# tc0xC_prod.net
KiCad netlist of a schematic drawn in EAGLE
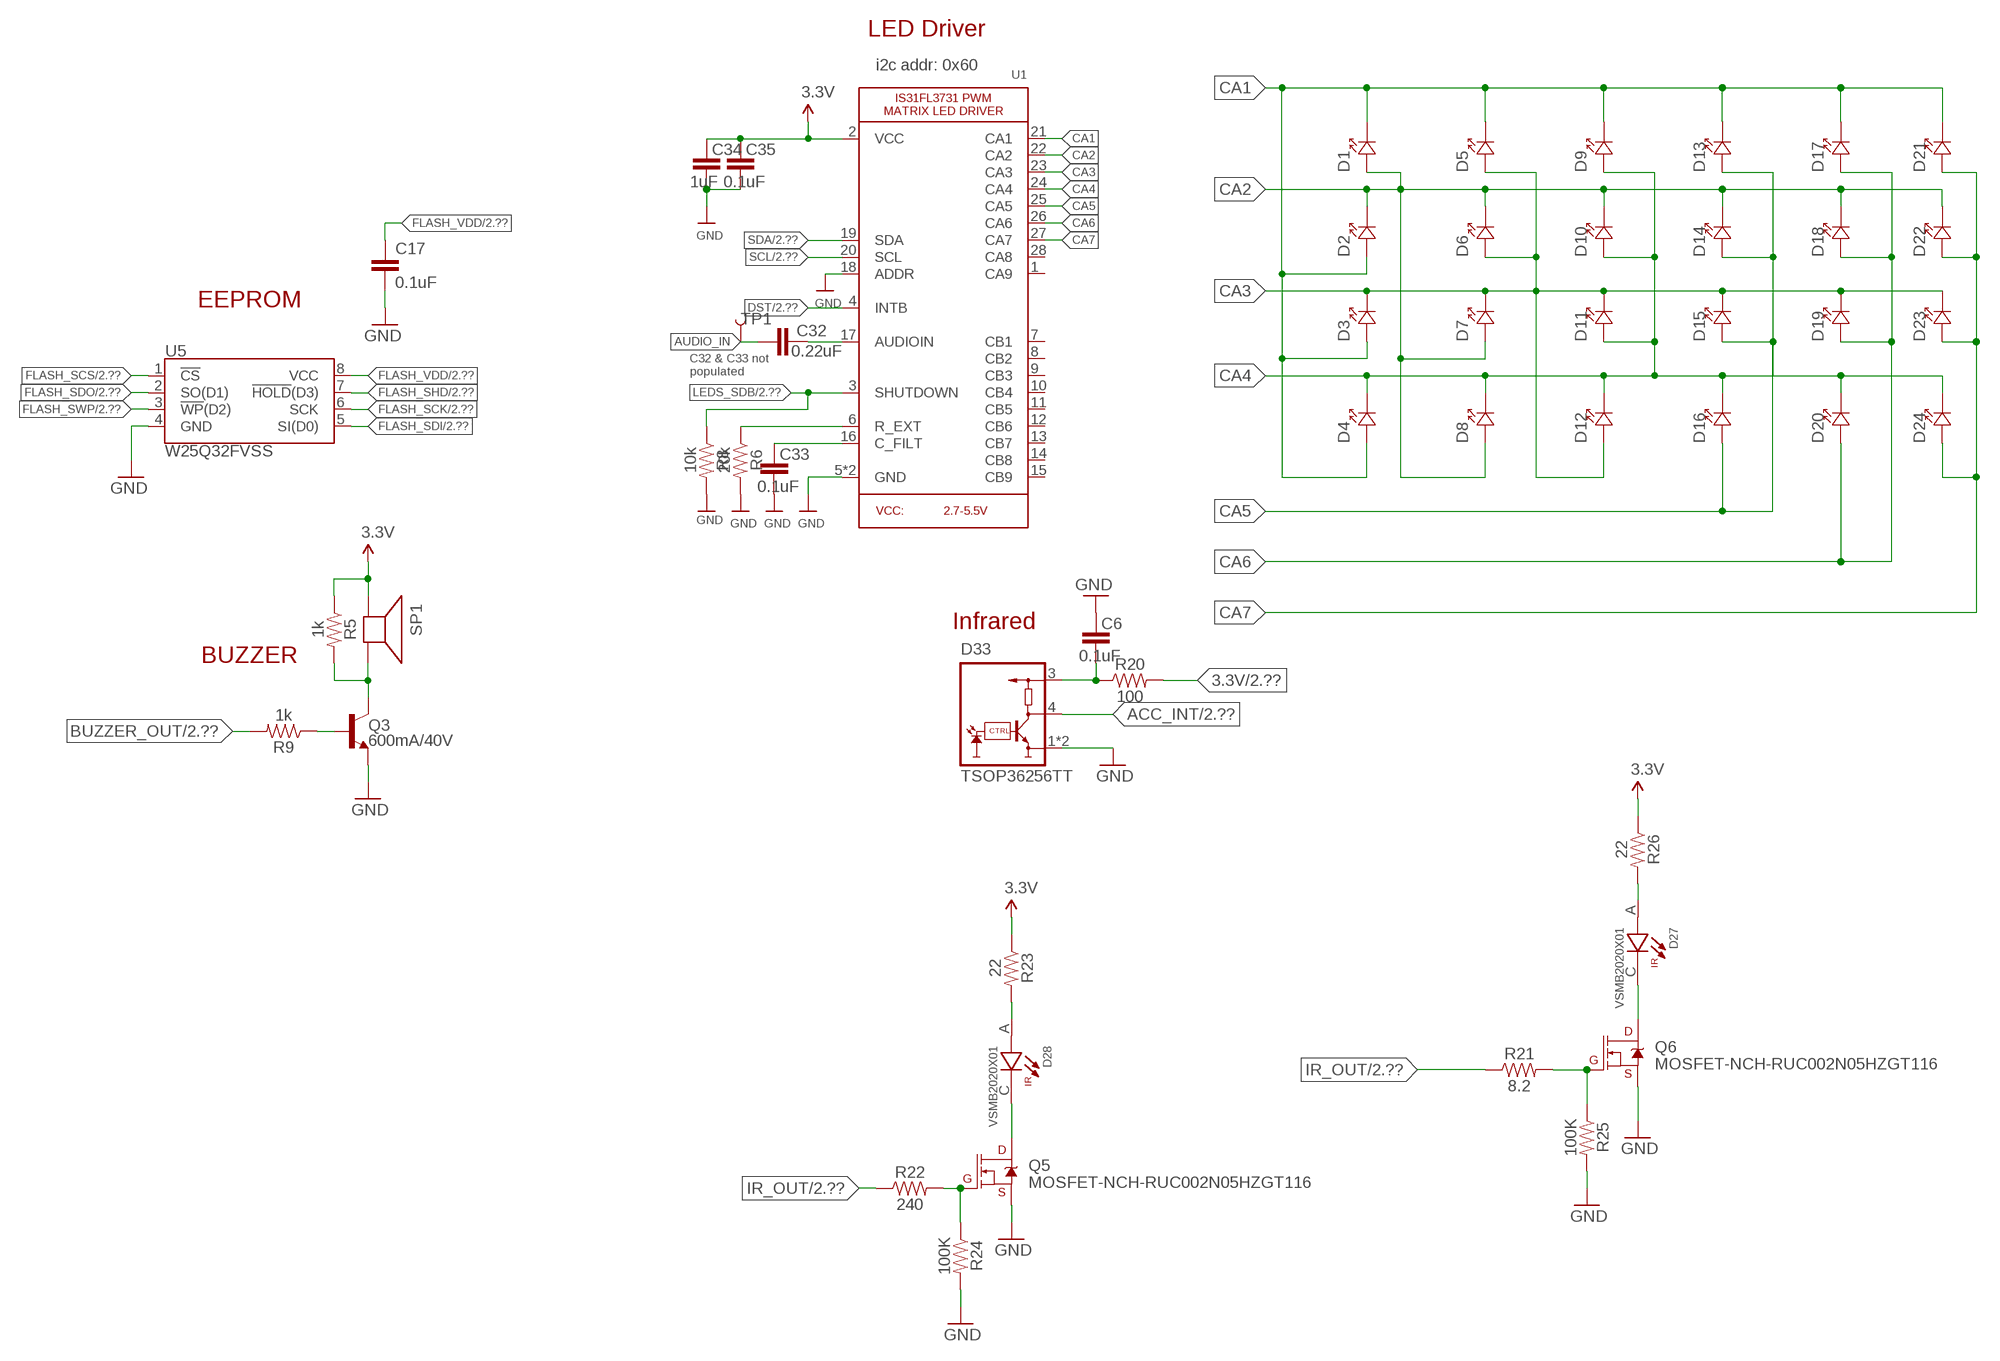
[diagram p0: schematic, sheet 1]
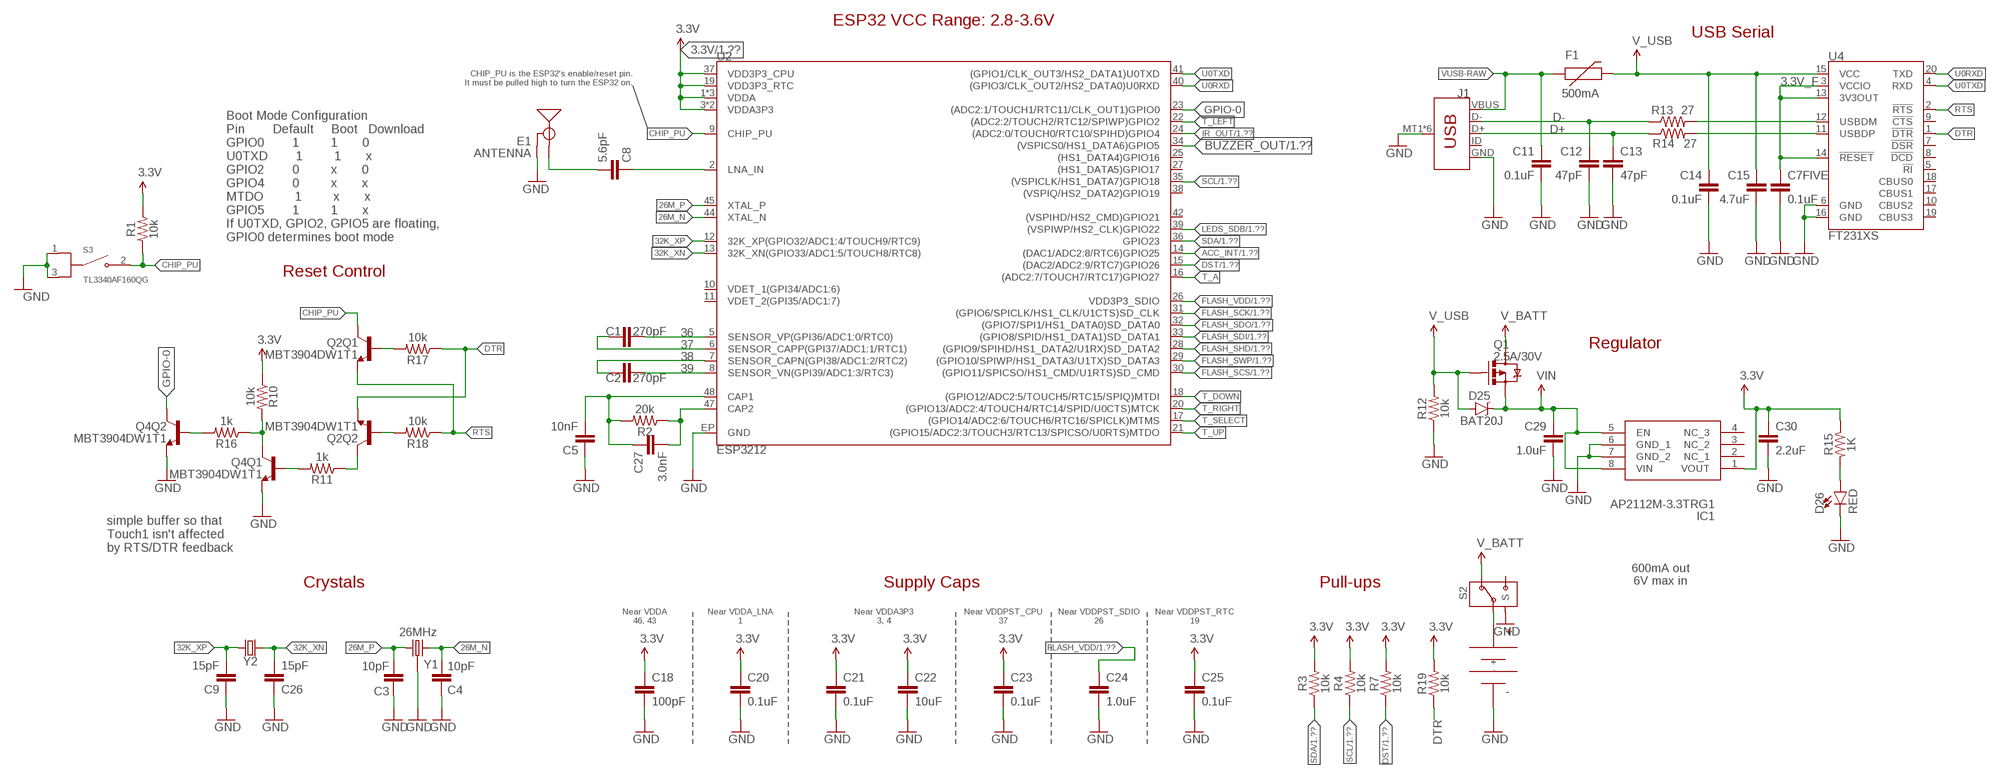
[diagram p1: schematic, sheet 2]

(export (version "E")
  (design (tool "Eeschema 10.0.6"))
  (components
    (comp (ref "C6")
      (value "0.1uF")
      (footprint "eagle-import:0603")
      (libsource (lib "eagle-import") (part "10PF-0603-50V-5%"))
    )
    (comp (ref "C17")
      (value "0.1uF")
      (footprint "eagle-import:0603")
      (libsource (lib "eagle-import") (part "0.1UF-0603-25V-(+80/-20%)"))
    )
    (comp (ref "C32")
      (value "0.22uF")
      (footprint "eagle-import:0603")
      (libsource (lib "eagle-import") (part "10PF-0603-50V-5%"))
    )
    (comp (ref "C33")
      (value "0.1uF")
      (footprint "eagle-import:0603")
      (libsource (lib "eagle-import") (part "10PF-0603-50V-5%"))
    )
    (comp (ref "C34")
      (value "1uF")
      (footprint "eagle-import:0603")
      (libsource (lib "eagle-import") (part "10PF-0603-50V-5%"))
    )
    (comp (ref "C35")
      (value "0.1uF")
      (footprint "eagle-import:0603")
      (libsource (lib "eagle-import") (part "10PF-0603-50V-5%"))
    )
    (comp (ref "D1")
      (value "LED-603")
      (footprint "eagle-import:SMD-603")
      (libsource (lib "eagle-import") (part "LED-603"))
    )
    (comp (ref "D2")
      (value "LED-603")
      (footprint "eagle-import:SMD-603")
      (libsource (lib "eagle-import") (part "LED-603"))
    )
    (comp (ref "D3")
      (value "LED-603")
      (footprint "eagle-import:SMD-603")
      (libsource (lib "eagle-import") (part "LED-603"))
    )
    (comp (ref "D4")
      (value "LED-603")
      (footprint "eagle-import:SMD-603")
      (libsource (lib "eagle-import") (part "LED-603"))
    )
    (comp (ref "D5")
      (value "LED-603")
      (footprint "eagle-import:SMD-603")
      (libsource (lib "eagle-import") (part "LED-603"))
    )
    (comp (ref "D6")
      (value "LED-603")
      (footprint "eagle-import:SMD-603")
      (libsource (lib "eagle-import") (part "LED-603"))
    )
    (comp (ref "D7")
      (value "LED-603")
      (footprint "eagle-import:SMD-603")
      (libsource (lib "eagle-import") (part "LED-603"))
    )
    (comp (ref "D8")
      (value "LED-603")
      (footprint "eagle-import:SMD-603")
      (libsource (lib "eagle-import") (part "LED-603"))
    )
    (comp (ref "D9")
      (value "LED-603")
      (footprint "eagle-import:SMD-603")
      (libsource (lib "eagle-import") (part "LED-603"))
    )
    (comp (ref "D10")
      (value "LED-603")
      (footprint "eagle-import:SMD-603")
      (libsource (lib "eagle-import") (part "LED-603"))
    )
    (comp (ref "D11")
      (value "LED-603")
      (footprint "eagle-import:SMD-603")
      (libsource (lib "eagle-import") (part "LED-603"))
    )
    (comp (ref "D12")
      (value "LED-603")
      (footprint "eagle-import:SMD-603")
      (libsource (lib "eagle-import") (part "LED-603"))
    )
    (comp (ref "D13")
      (value "LED-603")
      (footprint "eagle-import:SMD-603")
      (libsource (lib "eagle-import") (part "LED-603"))
    )
    (comp (ref "D14")
      (value "LED-603")
      (footprint "eagle-import:SMD-603")
      (libsource (lib "eagle-import") (part "LED-603"))
    )
    (comp (ref "D15")
      (value "LED-603")
      (footprint "eagle-import:SMD-603")
      (libsource (lib "eagle-import") (part "LED-603"))
    )
    (comp (ref "D16")
      (value "LED-603")
      (footprint "eagle-import:SMD-603")
      (libsource (lib "eagle-import") (part "LED-603"))
    )
    (comp (ref "D17")
      (value "LED-603")
      (footprint "eagle-import:SMD-603")
      (libsource (lib "eagle-import") (part "LED-603"))
    )
    (comp (ref "D18")
      (value "LED-603")
      (footprint "eagle-import:SMD-603")
      (libsource (lib "eagle-import") (part "LED-603"))
    )
    (comp (ref "D19")
      (value "LED-603")
      (footprint "eagle-import:SMD-603")
      (libsource (lib "eagle-import") (part "LED-603"))
    )
    (comp (ref "D20")
      (value "LED-603")
      (footprint "eagle-import:SMD-603")
      (libsource (lib "eagle-import") (part "LED-603"))
    )
    (comp (ref "D21")
      (value "LED-603")
      (footprint "eagle-import:SMD-603")
      (libsource (lib "eagle-import") (part "LED-603"))
    )
    (comp (ref "D22")
      (value "LED-603")
      (footprint "eagle-import:SMD-603")
      (libsource (lib "eagle-import") (part "LED-603"))
    )
    (comp (ref "D23")
      (value "LED-603")
      (footprint "eagle-import:SMD-603")
      (libsource (lib "eagle-import") (part "LED-603"))
    )
    (comp (ref "D24")
      (value "LED-603")
      (footprint "eagle-import:SMD-603")
      (libsource (lib "eagle-import") (part "LED-603"))
    )
    (comp (ref "D27")
      (value "VSMB2020X01")
      (footprint "eagle-import:DIO_VSMB2020X01")
      (fields (field (name "MF") "Vishay Semiconductors"))
      (libsource (lib "eagle-import") (part "VSMB2020X01"))
    )
    (comp (ref "D28")
      (value "VSMB2020X01")
      (footprint "eagle-import:DIO_VSMB2020X01")
      (fields (field (name "MF") "Vishay Semiconductors"))
      (libsource (lib "eagle-import") (part "VSMB2020X01"))
    )
    (comp (ref "D33")
      (value "TSOP36256TT")
      (footprint "eagle-import:TSOP36256")
      (fields (field (name "MF") "Vishay Semiconductors") (field (name "MP") "TSOP36256"))
      (libsource (lib "eagle-import") (part "TSOP36256TT"))
    )
    (comp (ref "Q3")
      (value "600mA/40V")
      (footprint "eagle-import:SOT23-3")
      (libsource (lib "eagle-import") (part "TRANS_NPN-MMBT2222AL"))
    )
    (comp (ref "Q5")
      (value "MOSFET-NCH-RUC002N05HZGT116")
      (footprint "eagle-import:SOT-23-3")
      (libsource (lib "eagle-import") (part "MOSFET-NCH-RUC002N05HZGT116"))
    )
    (comp (ref "Q6")
      (value "MOSFET-NCH-RUC002N05HZGT116")
      (footprint "eagle-import:SOT-23-3")
      (libsource (lib "eagle-import") (part "MOSFET-NCH-RUC002N05HZGT116"))
    )
    (comp (ref "R5")
      (value "1k")
      (footprint "eagle-import:0603")
      (libsource (lib "eagle-import") (part "10KOHM-0603-1/10W-1%"))
    )
    (comp (ref "R6")
      (value "20k")
      (footprint "eagle-import:0603")
      (libsource (lib "eagle-import") (part "10KOHM-0603-1/10W-1%"))
    )
    (comp (ref "R8")
      (value "10k")
      (footprint "eagle-import:0603")
      (libsource (lib "eagle-import") (part "10KOHM-0603-1/10W-1%"))
    )
    (comp (ref "R9")
      (value "1k")
      (footprint "eagle-import:0603")
      (libsource (lib "eagle-import") (part "10KOHM-0603-1/10W-1%"))
    )
    (comp (ref "R20")
      (value "100")
      (footprint "eagle-import:0603")
      (libsource (lib "eagle-import") (part "10KOHM-0603-1/10W-1%"))
    )
    (comp (ref "R21")
      (value "8.2")
      (footprint "eagle-import:0603")
      (libsource (lib "eagle-import") (part "10KOHM-0603-1/10W-1%"))
    )
    (comp (ref "R22")
      (value "240")
      (footprint "eagle-import:0603")
      (libsource (lib "eagle-import") (part "10KOHM-0603-1/10W-1%"))
    )
    (comp (ref "R23")
      (value "22")
      (footprint "eagle-import:0603")
      (libsource (lib "eagle-import") (part "10KOHM-0603-1/10W-1%"))
    )
    (comp (ref "R24")
      (value "100K")
      (footprint "eagle-import:0603")
      (libsource (lib "eagle-import") (part "10KOHM-0603-1/10W-1%"))
    )
    (comp (ref "R25")
      (value "100K")
      (footprint "eagle-import:0603")
      (libsource (lib "eagle-import") (part "10KOHM-0603-1/10W-1%"))
    )
    (comp (ref "R26")
      (value "22")
      (footprint "eagle-import:0603")
      (libsource (lib "eagle-import") (part "10KOHM-0603-1/10W-1%"))
    )
    (comp (ref "SP1")
      (value "SPEAKER/PS12")
      (footprint "eagle-import:PS12")
      (libsource (lib "eagle-import") (part "SPEAKER/PS12"))
    )
    (comp (ref "TP1")
      (value "TEST-POINT3X5")
      (footprint "eagle-import:PAD.03X.05")
      (libsource (lib "eagle-import") (part "TEST-POINT3X5"))
    )
    (comp (ref "U1")
      (value "IS31FL3731QFN")
      (footprint "eagle-import:QFN-28_4MM_0.4MM")
      (libsource (lib "eagle-import") (part "IS31FL3731QFN"))
    )
    (comp (ref "U5")
      (value "W25Q32FVSS")
      (footprint "eagle-import:SOIC-8")
      (libsource (lib "eagle-import") (part "W25Q32FVSS"))
    )
    (comp (ref "C1")
      (value "270pF")
      (footprint "eagle-import:0603")
      (libsource (lib "eagle-import") (part "270PF-50V-5%(0603)"))
    )
    (comp (ref "C2")
      (value "270pF")
      (footprint "eagle-import:0603")
      (libsource (lib "eagle-import") (part "270PF-50V-5%(0603)"))
    )
    (comp (ref "C3")
      (value "10pF")
      (footprint "eagle-import:0603")
      (libsource (lib "eagle-import") (part "10PF-0603-50V-5%"))
    )
    (comp (ref "C4")
      (value "10pF")
      (footprint "eagle-import:0603")
      (libsource (lib "eagle-import") (part "10PF-0603-50V-5%"))
    )
    (comp (ref "C5")
      (value "10nF")
      (footprint "eagle-import:0603")
      (libsource (lib "eagle-import") (part "10NF-0603-50V-10%"))
    )
    (comp (ref "C7FIVE")
      (value "0.1uF")
      (footprint "eagle-import:0603")
      (libsource (lib "eagle-import") (part "0.1UF-0603-25V-(+80/-20%)"))
    )
    (comp (ref "C8")
      (value "5.6pF")
      (footprint "eagle-import:0603")
      (libsource (lib "eagle-import") (part "5.6PF-50V-5%(0603)"))
    )
    (comp (ref "C9")
      (value "15pF")
      (footprint "eagle-import:0603")
      (libsource (lib "eagle-import") (part "15PF-0603-50V-5%"))
    )
    (comp (ref "C11")
      (value "0.1uF")
      (footprint "eagle-import:0603")
      (libsource (lib "eagle-import") (part "0.1UF-0603-25V-(+80/-20%)"))
    )
    (comp (ref "C12")
      (value "47pF")
      (footprint "eagle-import:0603")
      (libsource (lib "eagle-import") (part "47PF-0603-50V-5%"))
    )
    (comp (ref "C13")
      (value "47pF")
      (footprint "eagle-import:0603")
      (libsource (lib "eagle-import") (part "47PF-0603-50V-5%"))
    )
    (comp (ref "C14")
      (value "0.1uF")
      (footprint "eagle-import:0603")
      (libsource (lib "eagle-import") (part "0.1UF-0603-25V-(+80/-20%)"))
    )
    (comp (ref "C15")
      (value "4.7uF")
      (footprint "eagle-import:0603")
      (libsource (lib "eagle-import") (part "0.1UF-0603-25V-(+80/-20%)"))
    )
    (comp (ref "C18")
      (value "100pF")
      (footprint "eagle-import:0603")
      (libsource (lib "eagle-import") (part "100PF-0603-50V-5%"))
    )
    (comp (ref "C20")
      (value "0.1uF")
      (footprint "eagle-import:0603")
      (libsource (lib "eagle-import") (part "0.1UF-0603-25V-(+80/-20%)"))
    )
    (comp (ref "C21")
      (value "0.1uF")
      (footprint "eagle-import:0603")
      (libsource (lib "eagle-import") (part "0.1UF-0603-25V-(+80/-20%)"))
    )
    (comp (ref "C22")
      (value "10uF")
      (footprint "eagle-import:0603")
      (libsource (lib "eagle-import") (part "10UF-0603-6.3V-20%"))
    )
    (comp (ref "C23")
      (value "0.1uF")
      (footprint "eagle-import:0603")
      (libsource (lib "eagle-import") (part "0.1UF-0603-25V-(+80/-20%)"))
    )
    (comp (ref "C24")
      (value "1.0uF")
      (footprint "eagle-import:0603")
      (libsource (lib "eagle-import") (part "1.0UF-0603-16V-10%"))
    )
    (comp (ref "C25")
      (value "0.1uF")
      (footprint "eagle-import:0603")
      (libsource (lib "eagle-import") (part "0.1UF-0603-25V-(+80/-20%)"))
    )
    (comp (ref "C26")
      (value "15pF")
      (footprint "eagle-import:0603")
      (libsource (lib "eagle-import") (part "15PF-0603-50V-5%"))
    )
    (comp (ref "C27")
      (value "3.0nF")
      (footprint "eagle-import:0603")
      (libsource (lib "eagle-import") (part "3.0NF-0603-50V-5%"))
    )
    (comp (ref "C29")
      (value "1.0uF")
      (footprint "eagle-import:0805")
      (libsource (lib "eagle-import") (part "1.0UF-0805-25V-(+80/-20%)"))
    )
    (comp (ref "C30")
      (value "2.2uF")
      (footprint "eagle-import:0603")
      (libsource (lib "eagle-import") (part "2.2UF-0603-10V-20%"))
    )
    (comp (ref "D25")
      (value "BAT20J")
      (footprint "eagle-import:SOD-323")
      (libsource (lib "eagle-import") (part "DIODE-SCHOTTKY-BAT20J"))
    )
    (comp (ref "D26")
      (value "RED")
      (footprint "eagle-import:LED-0603@1")
      (libsource (lib "eagle-import") (part "LED-RED0603"))
    )
    (comp (ref "E1")
      (value "ANTENNA")
      (footprint "eagle-import:TRACE_ANTENNA_2.4GHZ_25.7MM_TUNED")
      (libsource (lib "eagle-import") (part "ANTENNATRACE-TUNED"))
    )
    (comp (ref "F1")
      (value "500mA")
      (footprint "eagle-import:PTC-1206")
      (libsource (lib "eagle-import") (part "PTCSMD"))
    )
    (comp (ref "G2")
      (value "KEYSTONE_2479")
      (footprint "eagle-import:KEYSTONE_2479")
      (libsource (lib "eagle-import") (part "KEYSTONE_2479"))
    )
    (comp (ref "IC1")
      (value "AP2112M-3.3TRG1")
      (footprint "eagle-import:SOIC127P600X170-8N")
      (fields (field (name "MOUSER_PART_NUMBER") "621-AP2112M-3.3TRG1"))
      (libsource (lib "eagle-import") (part "AP2112M-3.3TRG1"))
    )
    (comp (ref "J1")
      (value "USB_MICRO-B")
      (footprint "eagle-import:USB-MICROB-10118192")
      (libsource (lib "eagle-import") (part "USB_MICRO-B"))
    )
    (comp (ref "Q1")
      (value "2.5A/30V")
      (footprint "eagle-import:SOT23-3@1")
      (libsource (lib "eagle-import") (part "MOSFET-PCHANNELDMG2307L"))
    )
    (comp (ref "Q2")
      (value "MBT3904DW1T1")
      (footprint "eagle-import:SC70-6")
      (libsource (lib "eagle-import") (part "MBT3904DW1T1"))
    )
    (comp (ref "Q4")
      (value "MBT3904DW1T1")
      (footprint "eagle-import:SC70-6")
      (libsource (lib "eagle-import") (part "MBT3904DW1T1"))
    )
    (comp (ref "R1")
      (value "10k")
      (footprint "eagle-import:0603")
      (libsource (lib "eagle-import") (part "10KOHM-1/10W-1%(0603)0603"))
    )
    (comp (ref "R2")
      (value "20k")
      (footprint "eagle-import:0603")
      (libsource (lib "eagle-import") (part "20KOHM-0603-1/10W-1%"))
    )
    (comp (ref "R3")
      (value "10k")
      (footprint "eagle-import:0603")
      (libsource (lib "eagle-import") (part "10KOHM-0603-1/10W-1%"))
    )
    (comp (ref "R4")
      (value "10k")
      (footprint "eagle-import:0603")
      (libsource (lib "eagle-import") (part "10KOHM-0603-1/10W-1%"))
    )
    (comp (ref "R7")
      (value "10k")
      (footprint "eagle-import:0603")
      (libsource (lib "eagle-import") (part "10KOHM-0603-1/10W-1%"))
    )
    (comp (ref "R10")
      (value "10k")
      (footprint "eagle-import:0603")
      (libsource (lib "eagle-import") (part "10KOHM-0603-1/10W-1%"))
    )
    (comp (ref "R11")
      (value "1k")
      (footprint "eagle-import:0603")
      (libsource (lib "eagle-import") (part "10KOHM-0603-1/10W-1%"))
    )
    (comp (ref "R12")
      (value "10k")
      (footprint "eagle-import:0603")
      (libsource (lib "eagle-import") (part "10KOHM-0603-1/10W-1%"))
    )
    (comp (ref "R13")
      (value "27")
      (footprint "eagle-import:0603")
      (libsource (lib "eagle-import") (part "27OHM1/10W1%(0603)0603-RES"))
    )
    (comp (ref "R14")
      (value "27")
      (footprint "eagle-import:0603")
      (libsource (lib "eagle-import") (part "27OHM1/10W1%(0603)0603-RES"))
    )
    (comp (ref "R15")
      (value "1K")
      (footprint "eagle-import:0603")
      (libsource (lib "eagle-import") (part "1KOHM-1/10W-1%(0603)"))
    )
    (comp (ref "R16")
      (value "1k")
      (footprint "eagle-import:0603")
      (libsource (lib "eagle-import") (part "10KOHM-0603-1/10W-1%"))
    )
    (comp (ref "R17")
      (value "10k")
      (footprint "eagle-import:0603")
      (libsource (lib "eagle-import") (part "10KOHM-0603-1/10W-1%"))
    )
    (comp (ref "R18")
      (value "10k")
      (footprint "eagle-import:0603")
      (libsource (lib "eagle-import") (part "10KOHM-0603-1/10W-1%"))
    )
    (comp (ref "R19")
      (value "10k")
      (footprint "eagle-import:0603")
      (libsource (lib "eagle-import") (part "10KOHM-0603-1/10W-1%"))
    )
    (comp (ref "S2")
      (value "CUS-12B")
      (footprint "eagle-import:CUS-12_SPDT")
      (libsource (lib "eagle-import") (part "CUS-12B"))
    )
    (comp (ref "S3")
      (value "TL3340AF160QG")
      (footprint "eagle-import:SW_TL3340AF160QG")
      (fields (field (name "MF") "E-Switch"))
      (libsource (lib "eagle-import") (part "TL3340AF160QG"))
    )
    (comp (ref "U2")
      (value "ESP3212")
      (footprint "eagle-import:QFN48-0.4MM")
      (libsource (lib "eagle-import") (part "ESP3212"))
    )
    (comp (ref "U4")
      (value "FT231XS")
      (footprint "eagle-import:SSOP20_L")
      (libsource (lib "eagle-import") (part "FT231XS"))
    )
    (comp (ref "Y1")
      (value "26MHz")
      (footprint "eagle-import:CRYSTAL-SMD-3.2X2.5")
      (libsource (lib "eagle-import") (part "CRYSTAL-GROUNDED3.2X2.5"))
    )
    (comp (ref "Y2")
      (value "32.768kHz")
      (footprint "eagle-import:FC-12M")
      (libsource (lib "eagle-import") (part "FC-12M"))
    )
  )
  (nets
    (net (code "1") (name "3.3V") (class "Default")
      (node (ref "C18") (pin "1") (pinfunction "1_1") (pintype "passive"))
      (node (ref "C20") (pin "1") (pinfunction "1_1") (pintype "passive"))
      (node (ref "C21") (pin "1") (pinfunction "1_1") (pintype "passive"))
      (node (ref "C22") (pin "1") (pinfunction "1_1") (pintype "passive"))
      (node (ref "C23") (pin "1") (pinfunction "1_1") (pintype "passive"))
      (node (ref "C25") (pin "1") (pinfunction "1_1") (pintype "passive"))
      (node (ref "C30") (pin "1") (pinfunction "1_1") (pintype "passive"))
      (node (ref "C34") (pin "1") (pinfunction "1_1") (pintype "passive"))
      (node (ref "C35") (pin "1") (pinfunction "1_1") (pintype "passive"))
      (node (ref "IC1") (pin "1") (pinfunction "VOUT_1") (pintype "bidirectional"))
      (node (ref "R1") (pin "2") (pinfunction "2_2") (pintype "passive"))
      (node (ref "R10") (pin "1") (pinfunction "1_1") (pintype "passive"))
      (node (ref "R15") (pin "1") (pinfunction "1_1") (pintype "passive"))
      (node (ref "R19") (pin "2") (pinfunction "2_2") (pintype "passive"))
      (node (ref "R20") (pin "2") (pinfunction "2_2") (pintype "passive"))
      (node (ref "R23") (pin "1") (pinfunction "1_1") (pintype "passive"))
      (node (ref "R26") (pin "1") (pinfunction "1_1") (pintype "passive"))
      (node (ref "R3") (pin "2") (pinfunction "2_2") (pintype "passive"))
      (node (ref "R4") (pin "2") (pinfunction "2_2") (pintype "passive"))
      (node (ref "R5") (pin "1") (pinfunction "1_1") (pintype "passive"))
      (node (ref "R7") (pin "2") (pinfunction "2_2") (pintype "passive"))
      (node (ref "SP1") (pin "P$1") (pinfunction "+_P$1") (pintype "passive"))
      (node (ref "U1") (pin "2") (pinfunction "VCC_2") (pintype "power_in"))
      (node (ref "U2") (pin "1") (pinfunction "VDDA_1") (pintype "bidirectional"))
      (node (ref "U2") (pin "19") (pinfunction "VDD3P3_RTC_19") (pintype "bidirectional"))
      (node (ref "U2") (pin "3") (pinfunction "VDDA3P3_3") (pintype "bidirectional"))
      (node (ref "U2") (pin "37") (pinfunction "VDD3P3_CPU_37") (pintype "bidirectional"))
      (node (ref "U2") (pin "4") (pinfunction "VDDA3P3_4") (pintype "bidirectional"))
      (node (ref "U2") (pin "43") (pinfunction "VDDA_43") (pintype "bidirectional"))
      (node (ref "U2") (pin "46") (pinfunction "VDDA_46") (pintype "bidirectional"))
    )
    (net (code "2") (name "3.3V_F") (class "Default")
      (node (ref "C7FIVE") (pin "1") (pinfunction "1_1") (pintype "passive"))
      (node (ref "U4") (pin "13") (pinfunction "3V3OUT_13") (pintype "bidirectional"))
      (node (ref "U4") (pin "14") (pinfunction "~{RESET}_14") (pintype "bidirectional"))
      (node (ref "U4") (pin "3") (pinfunction "VCCIO_3") (pintype "bidirectional"))
    )
    (net (code "3") (name "26M_N") (class "Default")
      (node (ref "C4") (pin "2") (pinfunction "2_2") (pintype "passive"))
      (node (ref "U2") (pin "44") (pinfunction "XTAL_N_44") (pintype "bidirectional"))
      (node (ref "Y1") (pin "3") (pinfunction "2_3") (pintype "passive"))
    )
    (net (code "4") (name "26M_P") (class "Default")
      (node (ref "C3") (pin "2") (pinfunction "2_2") (pintype "passive"))
      (node (ref "U2") (pin "45") (pinfunction "XTAL_P_45") (pintype "bidirectional"))
      (node (ref "Y1") (pin "1") (pinfunction "1_1") (pintype "passive"))
    )
    (net (code "5") (name "32K_XN") (class "Default")
      (node (ref "C26") (pin "2") (pinfunction "2_2") (pintype "passive"))
      (node (ref "U2") (pin "13") (pinfunction "32K_XN(GPIO33/ADC1:5/TOUCH8/RTC8)_13") (pintype "bidirectional"))
      (node (ref "Y2") (pin "2") (pinfunction "2_2") (pintype "passive"))
    )
    (net (code "6") (name "32K_XP") (class "Default")
      (node (ref "C9") (pin "2") (pinfunction "2_2") (pintype "passive"))
      (node (ref "U2") (pin "12") (pinfunction "32K_XP(GPIO32/ADC1:4/TOUCH9/RTC9)_12") (pintype "bidirectional"))
      (node (ref "Y2") (pin "1") (pinfunction "1_1") (pintype "passive"))
    )
    (net (code "7") (name "36") (class "Default")
      (node (ref "C1") (pin "2") (pinfunction "2_2") (pintype "passive"))
      (node (ref "U2") (pin "5") (pinfunction "SENSOR_VP(GPI36/ADC1:0/RTC0)_5") (pintype "bidirectional"))
    )
    (net (code "8") (name "37") (class "Default")
      (node (ref "C1") (pin "1") (pinfunction "1_1") (pintype "passive"))
      (node (ref "U2") (pin "6") (pinfunction "SENSOR_CAPP(GPI37/ADC1:1/RTC1)_6") (pintype "bidirectional"))
    )
    (net (code "9") (name "38") (class "Default")
      (node (ref "C2") (pin "1") (pinfunction "1_1") (pintype "passive"))
      (node (ref "U2") (pin "7") (pinfunction "SENSOR_CAPN(GPI38/ADC1:2/RTC2)_7") (pintype "bidirectional"))
    )
    (net (code "10") (name "39") (class "Default")
      (node (ref "C2") (pin "2") (pinfunction "2_2") (pintype "passive"))
      (node (ref "U2") (pin "8") (pinfunction "SENSOR_VN(GPI39/ADC1:3/RTC3)_8") (pintype "bidirectional"))
    )
    (net (code "11") (name "ACC_INT") (class "Default")
      (node (ref "D33") (pin "4") (pinfunction "OUT_4") (pintype "output"))
      (node (ref "U2") (pin "14") (pinfunction "(DAC1/ADC2:8/RTC6)GPIO25_14") (pintype "bidirectional"))
    )
    (net (code "12") (name "AUDIO_IN") (class "Default")
      (node (ref "C32") (pin "1") (pinfunction "1_1") (pintype "passive"))
      (node (ref "TP1") (pin "P$1") (pinfunction "1_P$1") (pintype "bidirectional"))
    )
    (net (code "13") (name "BUZZER_OUT") (class "Default")
      (node (ref "R9") (pin "2") (pinfunction "2_2") (pintype "passive"))
      (node (ref "U2") (pin "34") (pinfunction "(VSPICS0/HS1_DATA6)GPIO5_34") (pintype "bidirectional"))
    )
    (net (code "14") (name "CA1") (class "Default")
      (node (ref "D1") (pin "P$2") (pinfunction "CATHODE-_P$2") (pintype "bidirectional"))
      (node (ref "D13") (pin "P$2") (pinfunction "CATHODE-_P$2") (pintype "bidirectional"))
      (node (ref "D17") (pin "P$2") (pinfunction "CATHODE-_P$2") (pintype "bidirectional"))
      (node (ref "D2") (pin "P$1") (pinfunction "ANODE+_P$1") (pintype "bidirectional"))
      (node (ref "D21") (pin "P$2") (pinfunction "CATHODE-_P$2") (pintype "bidirectional"))
      (node (ref "D3") (pin "P$1") (pinfunction "ANODE+_P$1") (pintype "bidirectional"))
      (node (ref "D4") (pin "P$1") (pinfunction "ANODE+_P$1") (pintype "bidirectional"))
      (node (ref "D5") (pin "P$2") (pinfunction "CATHODE-_P$2") (pintype "bidirectional"))
      (node (ref "D9") (pin "P$2") (pinfunction "CATHODE-_P$2") (pintype "bidirectional"))
      (node (ref "U1") (pin "21") (pinfunction "CA1_21") (pintype "bidirectional"))
    )
    (net (code "15") (name "CA2") (class "Default")
      (node (ref "D1") (pin "P$1") (pinfunction "ANODE+_P$1") (pintype "bidirectional"))
      (node (ref "D10") (pin "P$2") (pinfunction "CATHODE-_P$2") (pintype "bidirectional"))
      (node (ref "D14") (pin "P$2") (pinfunction "CATHODE-_P$2") (pintype "bidirectional"))
      (node (ref "D18") (pin "P$2") (pinfunction "CATHODE-_P$2") (pintype "bidirectional"))
      (node (ref "D2") (pin "P$2") (pinfunction "CATHODE-_P$2") (pintype "bidirectional"))
      (node (ref "D22") (pin "P$2") (pinfunction "CATHODE-_P$2") (pintype "bidirectional"))
      (node (ref "D6") (pin "P$2") (pinfunction "CATHODE-_P$2") (pintype "bidirectional"))
      (node (ref "D7") (pin "P$1") (pinfunction "ANODE+_P$1") (pintype "bidirectional"))
      (node (ref "D8") (pin "P$1") (pinfunction "ANODE+_P$1") (pintype "bidirectional"))
      (node (ref "U1") (pin "22") (pinfunction "CA2_22") (pintype "bidirectional"))
    )
    (net (code "16") (name "CA3") (class "Default")
      (node (ref "D11") (pin "P$2") (pinfunction "CATHODE-_P$2") (pintype "bidirectional"))
      (node (ref "D12") (pin "P$1") (pinfunction "ANODE+_P$1") (pintype "bidirectional"))
      (node (ref "D15") (pin "P$2") (pinfunction "CATHODE-_P$2") (pintype "bidirectional"))
      (node (ref "D19") (pin "P$2") (pinfunction "CATHODE-_P$2") (pintype "bidirectional"))
      (node (ref "D23") (pin "P$2") (pinfunction "CATHODE-_P$2") (pintype "bidirectional"))
      (node (ref "D3") (pin "P$2") (pinfunction "CATHODE-_P$2") (pintype "bidirectional"))
      (node (ref "D5") (pin "P$1") (pinfunction "ANODE+_P$1") (pintype "bidirectional"))
      (node (ref "D6") (pin "P$1") (pinfunction "ANODE+_P$1") (pintype "bidirectional"))
      (node (ref "D7") (pin "P$2") (pinfunction "CATHODE-_P$2") (pintype "bidirectional"))
      (node (ref "U1") (pin "23") (pinfunction "CA3_23") (pintype "bidirectional"))
    )
    (net (code "17") (name "CA4") (class "Default")
      (node (ref "D10") (pin "P$1") (pinfunction "ANODE+_P$1") (pintype "bidirectional"))
      (node (ref "D11") (pin "P$1") (pinfunction "ANODE+_P$1") (pintype "bidirectional"))
      (node (ref "D12") (pin "P$2") (pinfunction "CATHODE-_P$2") (pintype "bidirectional"))
      (node (ref "D16") (pin "P$2") (pinfunction "CATHODE-_P$2") (pintype "bidirectional"))
      (node (ref "D20") (pin "P$2") (pinfunction "CATHODE-_P$2") (pintype "bidirectional"))
      (node (ref "D24") (pin "P$2") (pinfunction "CATHODE-_P$2") (pintype "bidirectional"))
      (node (ref "D4") (pin "P$2") (pinfunction "CATHODE-_P$2") (pintype "bidirectional"))
      (node (ref "D8") (pin "P$2") (pinfunction "CATHODE-_P$2") (pintype "bidirectional"))
      (node (ref "D9") (pin "P$1") (pinfunction "ANODE+_P$1") (pintype "bidirectional"))
      (node (ref "U1") (pin "24") (pinfunction "CA4_24") (pintype "bidirectional"))
    )
    (net (code "18") (name "CA5") (class "Default")
      (node (ref "D13") (pin "P$1") (pinfunction "ANODE+_P$1") (pintype "bidirectional"))
      (node (ref "D14") (pin "P$1") (pinfunction "ANODE+_P$1") (pintype "bidirectional"))
      (node (ref "D15") (pin "P$1") (pinfunction "ANODE+_P$1") (pintype "bidirectional"))
      (node (ref "D16") (pin "P$1") (pinfunction "ANODE+_P$1") (pintype "bidirectional"))
      (node (ref "U1") (pin "25") (pinfunction "CA5_25") (pintype "bidirectional"))
    )
    (net (code "19") (name "CA6") (class "Default")
      (node (ref "D17") (pin "P$1") (pinfunction "ANODE+_P$1") (pintype "bidirectional"))
      (node (ref "D18") (pin "P$1") (pinfunction "ANODE+_P$1") (pintype "bidirectional"))
      (node (ref "D19") (pin "P$1") (pinfunction "ANODE+_P$1") (pintype "bidirectional"))
      (node (ref "D20") (pin "P$1") (pinfunction "ANODE+_P$1") (pintype "bidirectional"))
      (node (ref "U1") (pin "26") (pinfunction "CA6_26") (pintype "bidirectional"))
    )
    (net (code "20") (name "CA7") (class "Default")
      (node (ref "D21") (pin "P$1") (pinfunction "ANODE+_P$1") (pintype "bidirectional"))
      (node (ref "D22") (pin "P$1") (pinfunction "ANODE+_P$1") (pintype "bidirectional"))
      (node (ref "D23") (pin "P$1") (pinfunction "ANODE+_P$1") (pintype "bidirectional"))
      (node (ref "D24") (pin "P$1") (pinfunction "ANODE+_P$1") (pintype "bidirectional"))
      (node (ref "U1") (pin "27") (pinfunction "CA7_27") (pintype "bidirectional"))
    )
    (net (code "21") (name "CHIP_PU") (class "Default")
      (node (ref "Q2") (pin "3") (pinfunction "C_3") (pintype "passive"))
      (node (ref "R1") (pin "1") (pinfunction "1_1") (pintype "passive"))
      (node (ref "S3") (pin "2") (pinfunction "NO_2") (pintype "passive"))
      (node (ref "U2") (pin "9") (pinfunction "CHIP_PU_9") (pintype "bidirectional"))
    )
    (net (code "22") (name "D+") (class "Default")
      (node (ref "C13") (pin "1") (pinfunction "1_1") (pintype "passive"))
      (node (ref "J1") (pin "D+") (pinfunction "D+_D+") (pintype "bidirectional"))
      (node (ref "R14") (pin "1") (pinfunction "1_1") (pintype "passive"))
    )
    (net (code "23") (name "D-") (class "Default")
      (node (ref "C12") (pin "1") (pinfunction "1_1") (pintype "passive"))
      (node (ref "J1") (pin "D-") (pinfunction "D-_D-") (pintype "bidirectional"))
      (node (ref "R13") (pin "1") (pinfunction "1_1") (pintype "passive"))
    )
    (net (code "24") (name "DST") (class "Default")
      (node (ref "R7") (pin "1") (pinfunction "1_1") (pintype "passive"))
      (node (ref "U1") (pin "4") (pinfunction "INTB_4") (pintype "output"))
      (node (ref "U2") (pin "15") (pinfunction "(DAC2/ADC2:9/RTC7)GPIO26_15") (pintype "bidirectional"))
    )
    (net (code "25") (name "DTR") (class "Default")
      (node (ref "Q2") (pin "1") (pinfunction "E_1") (pintype "passive"))
      (node (ref "R17") (pin "1") (pinfunction "1_1") (pintype "passive"))
      (node (ref "R19") (pin "1") (pinfunction "1_1") (pintype "passive"))
      (node (ref "U4") (pin "1") (pinfunction "~{DTR}_1") (pintype "bidirectional"))
    )
    (net (code "26") (name "FLASH_SCK") (class "Default")
      (node (ref "U2") (pin "31") (pinfunction "(GPIO6/SPICLK/HS1_CLK/U1CTS)SD_CLK_31") (pintype "bidirectional"))
      (node (ref "U5") (pin "6") (pinfunction "SCK_6") (pintype "bidirectional"))
    )
    (net (code "27") (name "FLASH_SCS") (class "Default")
      (node (ref "U2") (pin "30") (pinfunction "(GPIO11/SPICSO/HS1_CMD/U1RTS)SD_CMD_30") (pintype "bidirectional"))
      (node (ref "U5") (pin "1") (pinfunction "~{CS}_1") (pintype "bidirectional"))
    )
    (net (code "28") (name "FLASH_SDI") (class "Default")
      (node (ref "U2") (pin "33") (pinfunction "(GPIO8/SPID/HS1_DATA1)SD_DATA1_33") (pintype "bidirectional"))
      (node (ref "U5") (pin "5") (pinfunction "SI(D0)_5") (pintype "bidirectional"))
    )
    (net (code "29") (name "FLASH_SDO") (class "Default")
      (node (ref "U2") (pin "32") (pinfunction "(GPIO7/SPI1/HS1_DATA0)SD_DATA0_32") (pintype "bidirectional"))
      (node (ref "U5") (pin "2") (pinfunction "SO(D1)_2") (pintype "bidirectional"))
    )
    (net (code "30") (name "FLASH_SHD") (class "Default")
      (node (ref "U2") (pin "28") (pinfunction "(GPIO9/SPIHD/HS1_DATA2/U1RX)SD_DATA2_28") (pintype "bidirectional"))
      (node (ref "U5") (pin "7") (pinfunction "~{HOLD}(D3)_7") (pintype "bidirectional"))
    )
    (net (code "31") (name "FLASH_SWP") (class "Default")
      (node (ref "U2") (pin "29") (pinfunction "(GPIO10/SPIWP/HS1_DATA3/U1TX)SD_DATA3_29") (pintype "bidirectional"))
      (node (ref "U5") (pin "3") (pinfunction "~{WP}(D2)_3") (pintype "bidirectional"))
    )
    (net (code "32") (name "FLASH_VDD") (class "Default")
      (node (ref "C17") (pin "1") (pinfunction "1_1") (pintype "passive"))
      (node (ref "C24") (pin "1") (pinfunction "1_1") (pintype "passive"))
      (node (ref "U2") (pin "26") (pinfunction "VDD3P3_SDIO_26") (pintype "bidirectional"))
      (node (ref "U5") (pin "8") (pinfunction "VCC_8") (pintype "bidirectional"))
    )
    (net (code "33") (name "GND") (class "Default")
      (node (ref "C11") (pin "2") (pinfunction "2_2") (pintype "passive"))
      (node (ref "C12") (pin "2") (pinfunction "2_2") (pintype "passive"))
      (node (ref "C13") (pin "2") (pinfunction "2_2") (pintype "passive"))
      (node (ref "C14") (pin "2") (pinfunction "2_2") (pintype "passive"))
      (node (ref "C15") (pin "2") (pinfunction "2_2") (pintype "passive"))
      (node (ref "C17") (pin "2") (pinfunction "2_2") (pintype "passive"))
      (node (ref "C18") (pin "2") (pinfunction "2_2") (pintype "passive"))
      (node (ref "C20") (pin "2") (pinfunction "2_2") (pintype "passive"))
      (node (ref "C21") (pin "2") (pinfunction "2_2") (pintype "passive"))
      (node (ref "C22") (pin "2") (pinfunction "2_2") (pintype "passive"))
      (node (ref "C23") (pin "2") (pinfunction "2_2") (pintype "passive"))
      (node (ref "C24") (pin "2") (pinfunction "2_2") (pintype "passive"))
      (node (ref "C25") (pin "2") (pinfunction "2_2") (pintype "passive"))
      (node (ref "C26") (pin "1") (pinfunction "1_1") (pintype "passive"))
      (node (ref "C29") (pin "2") (pinfunction "2_2") (pintype "passive"))
      (node (ref "C3") (pin "1") (pinfunction "1_1") (pintype "passive"))
      (node (ref "C30") (pin "2") (pinfunction "2_2") (pintype "passive"))
      (node (ref "C33") (pin "2") (pinfunction "2_2") (pintype "passive"))
      (node (ref "C34") (pin "2") (pinfunction "2_2") (pintype "passive"))
      (node (ref "C35") (pin "2") (pinfunction "2_2") (pintype "passive"))
      (node (ref "C4") (pin "1") (pinfunction "1_1") (pintype "passive"))
      (node (ref "C5") (pin "1") (pinfunction "1_1") (pintype "passive"))
      (node (ref "C6") (pin "1") (pinfunction "1_1") (pintype "passive"))
      (node (ref "C7FIVE") (pin "2") (pinfunction "2_2") (pintype "passive"))
      (node (ref "C9") (pin "1") (pinfunction "1_1") (pintype "passive"))
      (node (ref "D26") (pin "C") (pinfunction "C_C") (pintype "passive"))
      (node (ref "D33") (pin "1") (pinfunction "GND_1") (pintype "power_in"))
      (node (ref "D33") (pin "2") (pinfunction "GND_2") (pintype "power_in"))
      (node (ref "E1") (pin "GND") (pinfunction "GND_GND") (pintype "bidirectional"))
      (node (ref "E1") (pin "GND2") (pinfunction "GND_GND2") (pintype "bidirectional"))
      (node (ref "G2") (pin "-") (pinfunction "-_-") (pintype "bidirectional"))
      (node (ref "IC1") (pin "6") (pinfunction "GND_1_6") (pintype "bidirectional"))
      (node (ref "IC1") (pin "7") (pinfunction "GND_2_7") (pintype "bidirectional"))
      (node (ref "J1") (pin "GND") (pinfunction "GND_GND") (pintype "power_in"))
      (node (ref "J1") (pin "MT1") (pinfunction "SHIELD_MT1") (pintype "bidirectional"))
      (node (ref "J1") (pin "MT2") (pinfunction "SHIELD_MT2") (pintype "bidirectional"))
      (node (ref "J1") (pin "MT3") (pinfunction "SHIELD_MT3") (pintype "bidirectional"))
      (node (ref "J1") (pin "MT4") (pinfunction "SHIELD_MT4") (pintype "bidirectional"))
      (node (ref "J1") (pin "P$1") (pinfunction "SHIELD_P$1") (pintype "bidirectional"))
      (node (ref "J1") (pin "P$2") (pinfunction "SHIELD_P$2") (pintype "bidirectional"))
      (node (ref "Q3") (pin "2") (pinfunction "E_2") (pintype "passive"))
      (node (ref "Q4") (pin "1") (pinfunction "E_1") (pintype "passive"))
      (node (ref "Q4") (pin "4") (pinfunction "E_4") (pintype "passive"))
      (node (ref "Q5") (pin "2") (pinfunction "S_2") (pintype "bidirectional"))
      (node (ref "Q6") (pin "2") (pinfunction "S_2") (pintype "bidirectional"))
      (node (ref "R12") (pin "1") (pinfunction "1_1") (pintype "passive"))
      (node (ref "R24") (pin "2") (pinfunction "2_2") (pintype "passive"))
      (node (ref "R25") (pin "2") (pinfunction "2_2") (pintype "passive"))
      (node (ref "R6") (pin "2") (pinfunction "2_2") (pintype "passive"))
      (node (ref "R8") (pin "2") (pinfunction "2_2") (pintype "passive"))
      (node (ref "S2") (pin "P$4") (pinfunction "S_P$4") (pintype "bidirectional"))
      (node (ref "S2") (pin "P$5") (pinfunction "S_P$5") (pintype "bidirectional"))
      (node (ref "S2") (pin "P$6") (pinfunction "S_P$6") (pintype "bidirectional"))
      (node (ref "S2") (pin "P$7") (pinfunction "S_P$7") (pintype "bidirectional"))
      (node (ref "S3") (pin "1") (pinfunction "COM_1_1") (pintype "passive"))
      (node (ref "S3") (pin "3") (pinfunction "COM_2_3") (pintype "passive"))
      (node (ref "U1") (pin "18") (pinfunction "ADDR_18") (pintype "bidirectional"))
      (node (ref "U1") (pin "5") (pinfunction "GND_5") (pintype "power_in"))
      (node (ref "U1") (pin "THERMAL") (pinfunction "GND_THERMAL") (pintype "power_in"))
      (node (ref "U2") (pin "EP") (pinfunction "GND_EP") (pintype "bidirectional"))
      (node (ref "U4") (pin "16") (pinfunction "GND_16") (pintype "bidirectional"))
      (node (ref "U4") (pin "6") (pinfunction "GND_6") (pintype "bidirectional"))
      (node (ref "U5") (pin "4") (pinfunction "GND_4") (pintype "bidirectional"))
      (node (ref "Y1") (pin "2") (pinfunction "GND_2") (pintype "passive"))
      (node (ref "Y1") (pin "4") (pinfunction "GND_4") (pintype "passive"))
    )
    (net (code "34") (name "GPIO-0") (class "Default")
      (node (ref "Q4") (pin "6") (pinfunction "C_6") (pintype "passive"))
      (node (ref "U2") (pin "23") (pinfunction "(ADC2:1/TOUCH1/RTC11/CLK_OUT1)GPIO0_23") (pintype "bidirectional"))
    )
    (net (code "35") (name "IR_OUT") (class "Default")
      (node (ref "R21") (pin "1") (pinfunction "1_1") (pintype "passive"))
      (node (ref "R22") (pin "1") (pinfunction "1_1") (pintype "passive"))
      (node (ref "U2") (pin "24") (pinfunction "(ADC2:0/TOUCH0/RTC10/SPIHD)GPIO4_24") (pintype "bidirectional"))
    )
    (net (code "36") (name "LEDS_SDB") (class "Default")
      (node (ref "R8") (pin "1") (pinfunction "1_1") (pintype "passive"))
      (node (ref "U1") (pin "3") (pinfunction "SHUTDOWN_3") (pintype "input"))
      (node (ref "U2") (pin "39") (pinfunction "(VSPIWP/HS2_CLK)GPIO22_39") (pintype "bidirectional"))
    )
    (net (code "37") (name "Net-(D26-PadA)") (class "Default")
      (node (ref "D26") (pin "A") (pinfunction "A_A") (pintype "passive"))
      (node (ref "R15") (pin "2") (pinfunction "2_2") (pintype "passive"))
    )
    (net (code "38") (name "Net-(D27-PadA)") (class "Default")
      (node (ref "D27") (pin "A") (pinfunction "A_A") (pintype "passive"))
      (node (ref "R26") (pin "2") (pinfunction "2_2") (pintype "passive"))
    )
    (net (code "39") (name "Net-(D28-PadA)") (class "Default")
      (node (ref "D28") (pin "A") (pinfunction "A_A") (pintype "passive"))
      (node (ref "R23") (pin "2") (pinfunction "2_2") (pintype "passive"))
    )
    (net (code "40") (name "Net-(D33-VS)") (class "Default")
      (node (ref "C6") (pin "2") (pinfunction "2_2") (pintype "passive"))
      (node (ref "D33") (pin "3") (pinfunction "VS_3") (pintype "power_in"))
      (node (ref "R20") (pin "1") (pinfunction "1_1") (pintype "passive"))
    )
    (net (code "41") (name "Net-(E1-SIGNAL)") (class "Default")
      (node (ref "C8") (pin "2") (pinfunction "2_2") (pintype "passive"))
      (node (ref "E1") (pin "ANT") (pinfunction "SIGNAL_ANT") (pintype "bidirectional"))
    )
    (net (code "42") (name "Net-(Q2A-B)") (class "Default")
      (node (ref "Q2") (pin "5") (pinfunction "B_5") (pintype "passive"))
      (node (ref "R17") (pin "2") (pinfunction "2_2") (pintype "passive"))
    )
    (net (code "43") (name "Net-(Q2B-B)") (class "Default")
      (node (ref "Q2") (pin "2") (pinfunction "B_2") (pintype "passive"))
      (node (ref "R18") (pin "2") (pinfunction "2_2") (pintype "passive"))
    )
    (net (code "44") (name "Net-(Q2B-C)") (class "Default")
      (node (ref "Q2") (pin "6") (pinfunction "C_6") (pintype "passive"))
      (node (ref "R11") (pin "1") (pinfunction "1_1") (pintype "passive"))
    )
    (net (code "45") (name "Net-(Q3-B)") (class "Default")
      (node (ref "Q3") (pin "1") (pinfunction "B_1") (pintype "passive"))
      (node (ref "R9") (pin "1") (pinfunction "1_1") (pintype "passive"))
    )
    (net (code "46") (name "Net-(Q3-C)") (class "Default")
      (node (ref "Q3") (pin "3") (pinfunction "C_3") (pintype "passive"))
      (node (ref "R5") (pin "2") (pinfunction "2_2") (pintype "passive"))
      (node (ref "SP1") (pin "P$2") (pinfunction "-_P$2") (pintype "passive"))
    )
    (net (code "47") (name "Net-(Q4A-B)") (class "Default")
      (node (ref "Q4") (pin "5") (pinfunction "B_5") (pintype "passive"))
      (node (ref "R11") (pin "2") (pinfunction "2_2") (pintype "passive"))
    )
    (net (code "48") (name "Net-(Q4A-C)") (class "Default")
      (node (ref "Q4") (pin "3") (pinfunction "C_3") (pintype "passive"))
      (node (ref "R10") (pin "2") (pinfunction "2_2") (pintype "passive"))
      (node (ref "R16") (pin "1") (pinfunction "1_1") (pintype "passive"))
    )
    (net (code "49") (name "Net-(Q4B-B)") (class "Default")
      (node (ref "Q4") (pin "2") (pinfunction "B_2") (pintype "passive"))
      (node (ref "R16") (pin "2") (pinfunction "2_2") (pintype "passive"))
    )
    (net (code "50") (name "Net-(Q5-D)") (class "Default")
      (node (ref "D28") (pin "C") (pinfunction "C_C") (pintype "passive"))
      (node (ref "Q5") (pin "3") (pinfunction "D_3") (pintype "bidirectional"))
    )
    (net (code "51") (name "Net-(Q5-G)") (class "Default")
      (node (ref "Q5") (pin "1") (pinfunction "G_1") (pintype "bidirectional"))
      (node (ref "R22") (pin "2") (pinfunction "2_2") (pintype "passive"))
      (node (ref "R24") (pin "1") (pinfunction "1_1") (pintype "passive"))
    )
    (net (code "52") (name "Net-(Q6-D)") (class "Default")
      (node (ref "D27") (pin "C") (pinfunction "C_C") (pintype "passive"))
      (node (ref "Q6") (pin "3") (pinfunction "D_3") (pintype "bidirectional"))
    )
    (net (code "53") (name "Net-(Q6-G)") (class "Default")
      (node (ref "Q6") (pin "1") (pinfunction "G_1") (pintype "bidirectional"))
      (node (ref "R21") (pin "2") (pinfunction "2_2") (pintype "passive"))
      (node (ref "R25") (pin "1") (pinfunction "1_1") (pintype "passive"))
    )
    (net (code "54") (name "Net-(S2-1)") (class "Default")
      (node (ref "G2") (pin "+") (pinfunction "+_+") (pintype "bidirectional"))
      (node (ref "S2") (pin "P$2") (pinfunction "1_P$2") (pintype "bidirectional"))
    )
    (net (code "55") (name "Net-(U1-AUDIOIN)") (class "Default")
      (node (ref "C32") (pin "2") (pinfunction "2_2") (pintype "passive"))
      (node (ref "U1") (pin "17") (pinfunction "AUDIOIN_17") (pintype "input"))
    )
    (net (code "56") (name "Net-(U1-C_FILT)") (class "Default")
      (node (ref "C33") (pin "1") (pinfunction "1_1") (pintype "passive"))
      (node (ref "U1") (pin "16") (pinfunction "C_FILT_16") (pintype "bidirectional"))
    )
    (net (code "57") (name "Net-(U1-R_EXT)") (class "Default")
      (node (ref "R6") (pin "1") (pinfunction "1_1") (pintype "passive"))
      (node (ref "U1") (pin "6") (pinfunction "R_EXT_6") (pintype "bidirectional"))
    )
    (net (code "58") (name "Net-(U2-CAP1)") (class "Default")
      (node (ref "C27") (pin "1") (pinfunction "1_1") (pintype "passive"))
      (node (ref "C5") (pin "2") (pinfunction "2_2") (pintype "passive"))
      (node (ref "R2") (pin "2") (pinfunction "2_2") (pintype "passive"))
      (node (ref "U2") (pin "48") (pinfunction "CAP1_48") (pintype "bidirectional"))
    )
    (net (code "59") (name "Net-(U2-CAP2)") (class "Default")
      (node (ref "C27") (pin "2") (pinfunction "2_2") (pintype "passive"))
      (node (ref "R2") (pin "1") (pinfunction "1_1") (pintype "passive"))
      (node (ref "U2") (pin "47") (pinfunction "CAP2_47") (pintype "bidirectional"))
    )
    (net (code "60") (name "Net-(U2-LNA_IN)") (class "Default")
      (node (ref "C8") (pin "1") (pinfunction "1_1") (pintype "passive"))
      (node (ref "U2") (pin "2") (pinfunction "LNA_IN_2") (pintype "bidirectional"))
    )
    (net (code "61") (name "Net-(U4-USBDM)") (class "Default")
      (node (ref "R13") (pin "2") (pinfunction "2_2") (pintype "passive"))
      (node (ref "U4") (pin "12") (pinfunction "USBDM_12") (pintype "bidirectional"))
    )
    (net (code "62") (name "Net-(U4-USBDP)") (class "Default")
      (node (ref "R14") (pin "2") (pinfunction "2_2") (pintype "passive"))
      (node (ref "U4") (pin "11") (pinfunction "USBDP_11") (pintype "bidirectional"))
    )
    (net (code "63") (name "RTS") (class "Default")
      (node (ref "Q2") (pin "4") (pinfunction "E_4") (pintype "passive"))
      (node (ref "R18") (pin "1") (pinfunction "1_1") (pintype "passive"))
      (node (ref "U4") (pin "2") (pinfunction "~{RTS}_2") (pintype "bidirectional"))
    )
    (net (code "64") (name "SCL") (class "Default")
      (node (ref "R4") (pin "1") (pinfunction "1_1") (pintype "passive"))
      (node (ref "U1") (pin "20") (pinfunction "SCL_20") (pintype "bidirectional"))
      (node (ref "U2") (pin "35") (pinfunction "(VSPICLK/HS1_DATA7)GPIO18_35") (pintype "bidirectional"))
    )
    (net (code "65") (name "SDA") (class "Default")
      (node (ref "R3") (pin "1") (pinfunction "1_1") (pintype "passive"))
      (node (ref "U1") (pin "19") (pinfunction "SDA_19") (pintype "bidirectional"))
      (node (ref "U2") (pin "36") (pinfunction "GPIO23_36") (pintype "bidirectional"))
    )
    (net (code "66") (name "T_A") (class "Default")
      (node (ref "U2") (pin "16") (pinfunction "(ADC2:7/TOUCH7/RTC17)GPIO27_16") (pintype "bidirectional"))
    )
    (net (code "67") (name "T_DOWN") (class "Default")
      (node (ref "U2") (pin "18") (pinfunction "(GPIO12/ADC2:5/TOUCH5/RTC15/SPIQ)MTDI_18") (pintype "bidirectional"))
    )
    (net (code "68") (name "T_LEFT") (class "Default")
      (node (ref "U2") (pin "22") (pinfunction "(ADC2:2/TOUCH2/RTC12/SPIWP)GPIO2_22") (pintype "bidirectional"))
    )
    (net (code "69") (name "T_RIGHT") (class "Default")
      (node (ref "U2") (pin "20") (pinfunction "(GPIO13/ADC2:4/TOUCH4/RTC14/SPID/U0CTS)MTCK_20") (pintype "bidirectional"))
    )
    (net (code "70") (name "T_SELECT") (class "Default")
      (node (ref "U2") (pin "17") (pinfunction "(GPIO14/ADC2:6/TOUCH6/RTC16/SPICLK)MTMS_17") (pintype "bidirectional"))
    )
    (net (code "71") (name "T_UP") (class "Default")
      (node (ref "U2") (pin "21") (pinfunction "(GPIO15/ADC2:3/TOUCH3/RTC13/SPICSO/U0RTS)MTDO_21") (pintype "bidirectional"))
    )
    (net (code "72") (name "U0RXD") (class "Default")
      (node (ref "U2") (pin "40") (pinfunction "(GPIO3/CLK_OUT2/HS2_DATA0)U0RXD_40") (pintype "bidirectional"))
      (node (ref "U4") (pin "20") (pinfunction "TXD_20") (pintype "bidirectional"))
    )
    (net (code "73") (name "U0TXD") (class "Default")
      (node (ref "U2") (pin "41") (pinfunction "(GPIO1/CLK_OUT3/HS2_DATA1)U0TXD_41") (pintype "bidirectional"))
      (node (ref "U4") (pin "4") (pinfunction "RXD_4") (pintype "bidirectional"))
    )
    (net (code "74") (name "VIN") (class "Default")
      (node (ref "C29") (pin "1") (pinfunction "1_1") (pintype "passive"))
      (node (ref "D25") (pin "C") (pinfunction "C_C") (pintype "passive"))
      (node (ref "IC1") (pin "5") (pinfunction "EN_5") (pintype "bidirectional"))
      (node (ref "IC1") (pin "8") (pinfunction "VIN_8") (pintype "bidirectional"))
      (node (ref "Q1") (pin "2") (pinfunction "S_2") (pintype "passive"))
    )
    (net (code "75") (name "VUSB-RAW") (class "Default")
      (node (ref "C11") (pin "1") (pinfunction "1_1") (pintype "passive"))
      (node (ref "F1") (pin "1") (pinfunction "1_1") (pintype "bidirectional"))
      (node (ref "J1") (pin "VBUS") (pinfunction "VBUS_VBUS") (pintype "power_in"))
    )
    (net (code "76") (name "V_BATT") (class "Default")
      (node (ref "Q1") (pin "3") (pinfunction "D_3") (pintype "passive"))
      (node (ref "S2") (pin "P$1") (pinfunction "2_P$1") (pintype "bidirectional"))
    )
    (net (code "77") (name "V_USB") (class "Default")
      (node (ref "C14") (pin "1") (pinfunction "1_1") (pintype "passive"))
      (node (ref "C15") (pin "1") (pinfunction "1_1") (pintype "passive"))
      (node (ref "D25") (pin "A") (pinfunction "A_A") (pintype "passive"))
      (node (ref "F1") (pin "2") (pinfunction "2_2") (pintype "bidirectional"))
      (node (ref "Q1") (pin "1") (pinfunction "G_1") (pintype "passive"))
      (node (ref "R12") (pin "2") (pinfunction "2_2") (pintype "passive"))
      (node (ref "U4") (pin "15") (pinfunction "VCC_15") (pintype "bidirectional"))
    )
    (net (code "78") (name "unconnected-(IC1-NC_1-Pad2)") (class "Default")
      (node (ref "IC1") (pin "2") (pinfunction "NC_1_2") (pintype "bidirectional"))
    )
    (net (code "79") (name "unconnected-(IC1-NC_2-Pad3)") (class "Default")
      (node (ref "IC1") (pin "3") (pinfunction "NC_2_3") (pintype "bidirectional"))
    )
    (net (code "80") (name "unconnected-(IC1-NC_3-Pad4)") (class "Default")
      (node (ref "IC1") (pin "4") (pinfunction "NC_3_4") (pintype "bidirectional"))
    )
    (net (code "81") (name "unconnected-(J1-PadID)") (class "Default")
      (node (ref "J1") (pin "ID") (pinfunction "ID_ID") (pintype "bidirectional"))
    )
    (net (code "82") (name "unconnected-(S2-3-PadP$3)") (class "Default")
      (node (ref "S2") (pin "P$3") (pinfunction "3_P$3") (pintype "bidirectional"))
    )
    (net (code "83") (name "unconnected-(U1-CA8-Pad28)") (class "Default")
      (node (ref "U1") (pin "28") (pinfunction "CA8_28") (pintype "bidirectional"))
    )
    (net (code "84") (name "unconnected-(U1-CA9-Pad1)") (class "Default")
      (node (ref "U1") (pin "1") (pinfunction "CA9_1") (pintype "bidirectional"))
    )
    (net (code "85") (name "unconnected-(U1-CB1-Pad7)") (class "Default")
      (node (ref "U1") (pin "7") (pinfunction "CB1_7") (pintype "bidirectional"))
    )
    (net (code "86") (name "unconnected-(U1-CB2-Pad8)") (class "Default")
      (node (ref "U1") (pin "8") (pinfunction "CB2_8") (pintype "bidirectional"))
    )
    (net (code "87") (name "unconnected-(U1-CB3-Pad9)") (class "Default")
      (node (ref "U1") (pin "9") (pinfunction "CB3_9") (pintype "bidirectional"))
    )
    (net (code "88") (name "unconnected-(U1-CB4-Pad10)") (class "Default")
      (node (ref "U1") (pin "10") (pinfunction "CB4_10") (pintype "bidirectional"))
    )
    (net (code "89") (name "unconnected-(U1-CB5-Pad11)") (class "Default")
      (node (ref "U1") (pin "11") (pinfunction "CB5_11") (pintype "bidirectional"))
    )
    (net (code "90") (name "unconnected-(U1-CB6-Pad12)") (class "Default")
      (node (ref "U1") (pin "12") (pinfunction "CB6_12") (pintype "bidirectional"))
    )
    (net (code "91") (name "unconnected-(U1-CB7-Pad13)") (class "Default")
      (node (ref "U1") (pin "13") (pinfunction "CB7_13") (pintype "bidirectional"))
    )
    (net (code "92") (name "unconnected-(U1-CB8-Pad14)") (class "Default")
      (node (ref "U1") (pin "14") (pinfunction "CB8_14") (pintype "bidirectional"))
    )
    (net (code "93") (name "unconnected-(U1-CB9-Pad15)") (class "Default")
      (node (ref "U1") (pin "15") (pinfunction "CB9_15") (pintype "bidirectional"))
    )
    (net (code "94") (name "unconnected-(U2-(HS1_DATA4)GPIO16-Pad25)") (class "Default")
      (node (ref "U2") (pin "25") (pinfunction "(HS1_DATA4)GPIO16_25") (pintype "bidirectional"))
    )
    (net (code "95") (name "unconnected-(U2-(HS1_DATA5)GPIO17-Pad27)") (class "Default")
      (node (ref "U2") (pin "27") (pinfunction "(HS1_DATA5)GPIO17_27") (pintype "bidirectional"))
    )
    (net (code "96") (name "unconnected-(U2-(VSPIHD{slash}HS2_CMD)GPIO21-Pad42)") (class "Default")
      (node (ref "U2") (pin "42") (pinfunction "(VSPIHD/HS2_CMD)GPIO21_42") (pintype "bidirectional"))
    )
    (net (code "97") (name "unconnected-(U2-(VSPIQ{slash}HS2_DATA2)GPIO19-Pad38)") (class "Default")
      (node (ref "U2") (pin "38") (pinfunction "(VSPIQ/HS2_DATA2)GPIO19_38") (pintype "bidirectional"))
    )
    (net (code "98") (name "unconnected-(U2-VDET_1(GPI34{slash}ADC1:6)-Pad10)") (class "Default")
      (node (ref "U2") (pin "10") (pinfunction "VDET_1(GPI34/ADC1:6)_10") (pintype "bidirectional"))
    )
    (net (code "99") (name "unconnected-(U2-VDET_2(GPI35{slash}ADC1:7)-Pad11)") (class "Default")
      (node (ref "U2") (pin "11") (pinfunction "VDET_2(GPI35/ADC1:7)_11") (pintype "bidirectional"))
    )
    (net (code "100") (name "unconnected-(U4-CBUS0-Pad18)") (class "Default")
      (node (ref "U4") (pin "18") (pinfunction "CBUS0_18") (pintype "bidirectional"))
    )
    (net (code "101") (name "unconnected-(U4-CBUS1-Pad17)") (class "Default")
      (node (ref "U4") (pin "17") (pinfunction "CBUS1_17") (pintype "bidirectional"))
    )
    (net (code "102") (name "unconnected-(U4-CBUS2-Pad10)") (class "Default")
      (node (ref "U4") (pin "10") (pinfunction "CBUS2_10") (pintype "bidirectional"))
    )
    (net (code "103") (name "unconnected-(U4-CBUS3-Pad19)") (class "Default")
      (node (ref "U4") (pin "19") (pinfunction "CBUS3_19") (pintype "bidirectional"))
    )
    (net (code "104") (name "unconnected-(U4-~{CTS}-Pad9)") (class "Default")
      (node (ref "U4") (pin "9") (pinfunction "~{CTS}_9") (pintype "bidirectional"))
    )
    (net (code "105") (name "unconnected-(U4-~{DCD}-Pad8)") (class "Default")
      (node (ref "U4") (pin "8") (pinfunction "~{DCD}_8") (pintype "bidirectional"))
    )
    (net (code "106") (name "unconnected-(U4-~{DSR}-Pad7)") (class "Default")
      (node (ref "U4") (pin "7") (pinfunction "~{DSR}_7") (pintype "bidirectional"))
    )
    (net (code "107") (name "unconnected-(U4-~{RI}-Pad5)") (class "Default")
      (node (ref "U4") (pin "5") (pinfunction "~{RI}_5") (pintype "bidirectional"))
    )
  )
)
